# IO_Buffer.net
KiCad netlist of a schematic drawn in EAGLE
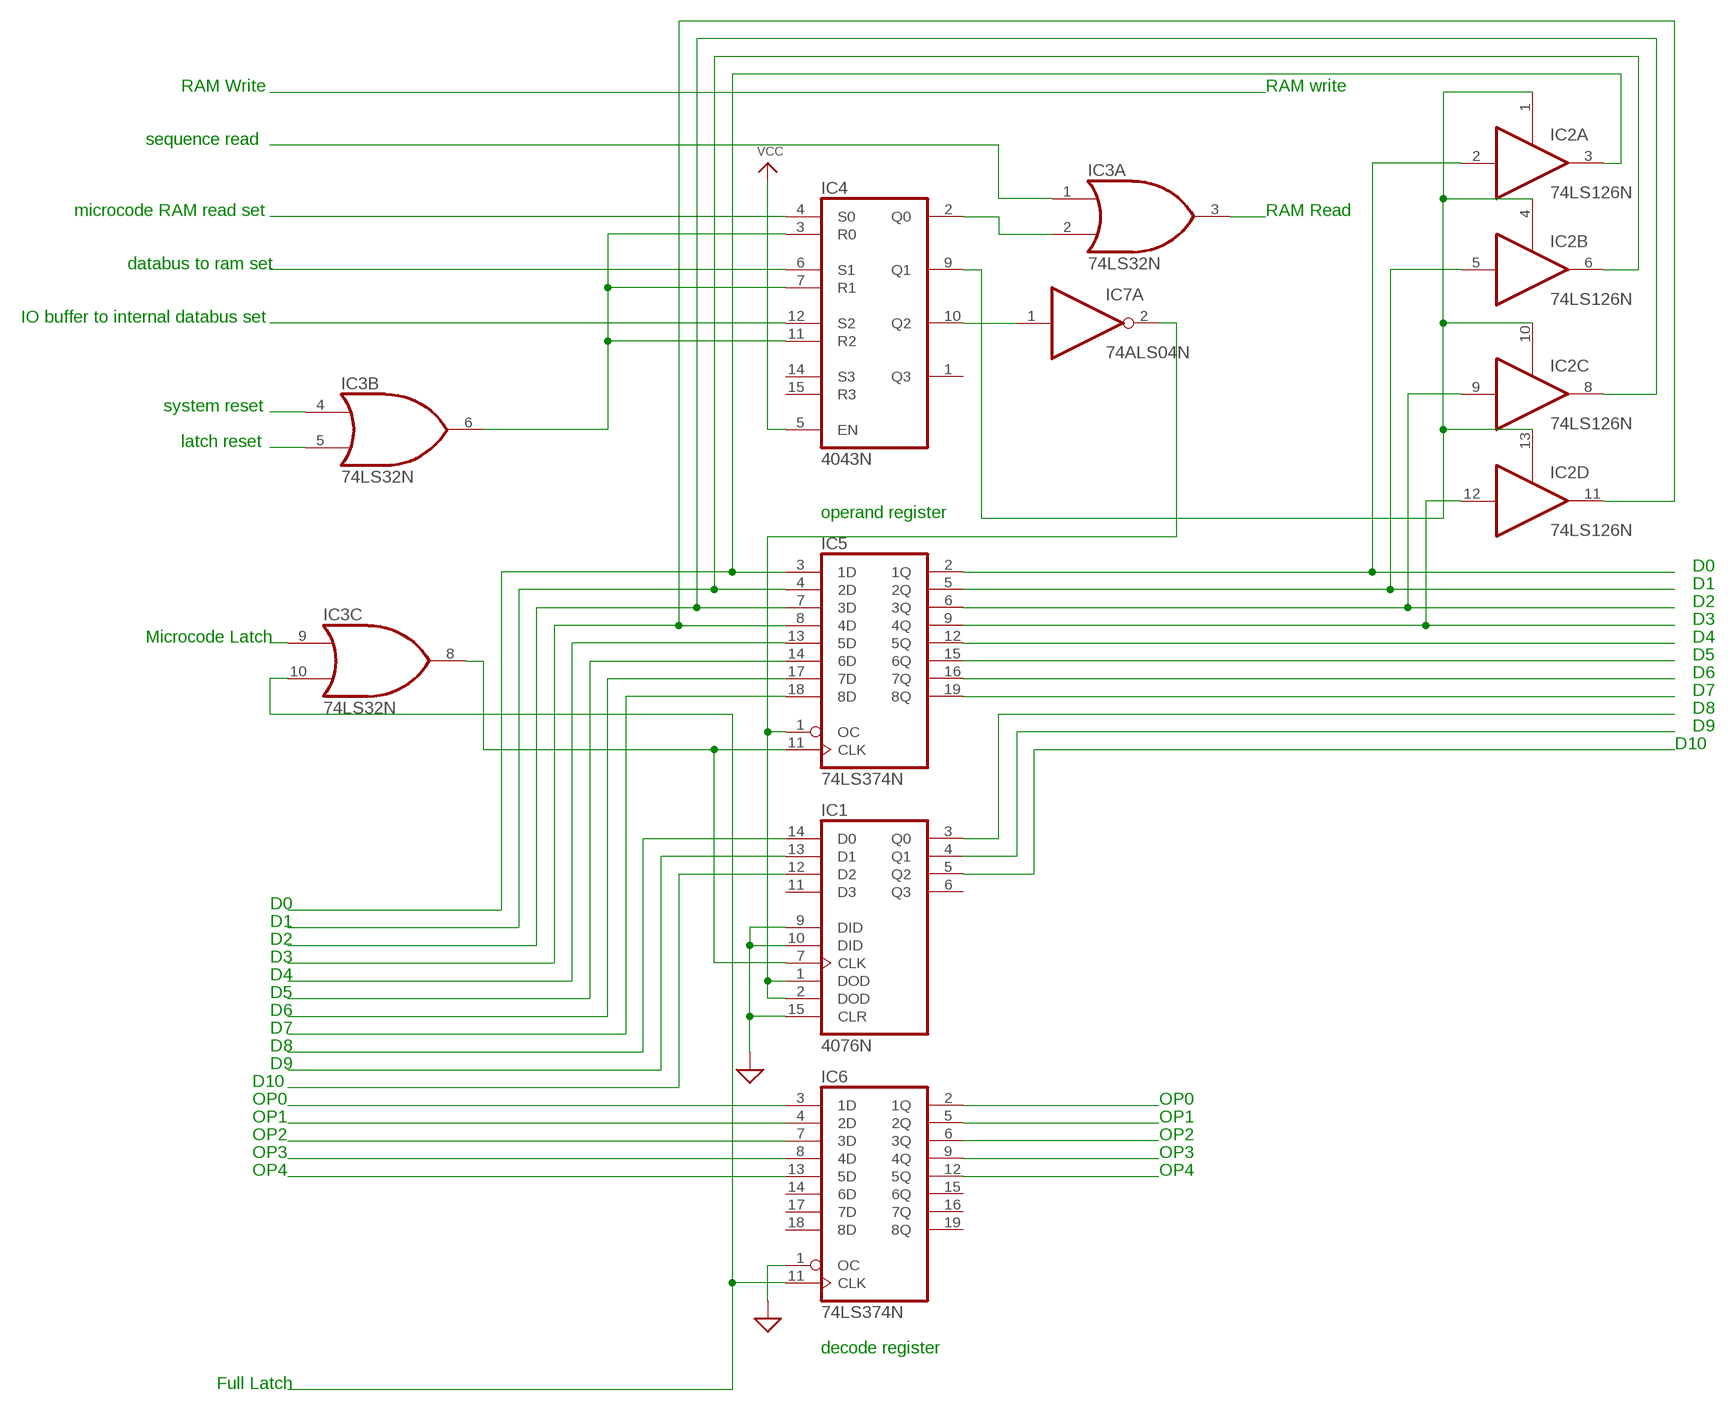
[diagram p0: schematic, sheet 1]

(export (version "E")
  (design (tool "Eeschema 10.0.6"))
  (components
    (comp (ref "IC1")
      (value "4076N")
      (footprint "eagle-import:DIL16")
      (libsource (lib "eagle-import") (part "4076N"))
    )
    (comp (ref "IC2")
      (value "74LS126N")
      (footprint "eagle-import:DIL14")
      (libsource (lib "eagle-import") (part "74126NLS"))
    )
    (comp (ref "IC3")
      (value "74LS32N")
      (footprint "eagle-import:DIL14")
      (libsource (lib "eagle-import") (part "7432NLS"))
    )
    (comp (ref "IC4")
      (value "4043N")
      (footprint "eagle-import:DIL16")
      (libsource (lib "eagle-import") (part "4043N"))
    )
    (comp (ref "IC5")
      (value "74LS374N")
      (footprint "eagle-import:DIL20")
      (libsource (lib "eagle-import") (part "74374NLS"))
    )
    (comp (ref "IC6")
      (value "74LS374N")
      (footprint "eagle-import:DIL20")
      (libsource (lib "eagle-import") (part "74374NLS"))
    )
    (comp (ref "IC7")
      (value "74ALS04N")
      (footprint "eagle-import:DIL14")
      (libsource (lib "eagle-import") (part "7404NALS"))
    )
  )
  (nets
    (net (code "1") (name "Net-(IC1A-CLK)") (class "Default")
      (node (ref "IC1") (pin "7") (pinfunction "CLK_7") (pintype "input"))
      (node (ref "IC3") (pin "8") (pinfunction "O_8") (pintype "output"))
      (node (ref "IC5") (pin "11") (pinfunction "CLK_11") (pintype "input"))
    )
    (net (code "2") (name "Net-(IC2A-I)") (class "Default")
      (node (ref "IC2") (pin "2") (pinfunction "I_2") (pintype "input"))
      (node (ref "IC5") (pin "2") (pinfunction "1Q_2") (pintype "tri_state"))
    )
    (net (code "3") (name "Net-(IC2A-O)") (class "Default")
      (node (ref "IC2") (pin "3") (pinfunction "O_3") (pintype "output"))
      (node (ref "IC5") (pin "3") (pinfunction "1D_3") (pintype "input"))
    )
    (net (code "4") (name "Net-(IC2A-OE)") (class "Default")
      (node (ref "IC2") (pin "1") (pinfunction "OE_1") (pintype "input"))
      (node (ref "IC2") (pin "10") (pinfunction "OE_10") (pintype "input"))
      (node (ref "IC2") (pin "13") (pinfunction "OE_13") (pintype "input"))
      (node (ref "IC2") (pin "4") (pinfunction "OE_4") (pintype "input"))
      (node (ref "IC4") (pin "9") (pinfunction "Q1_9") (pintype "output"))
    )
    (net (code "5") (name "Net-(IC2B-I)") (class "Default")
      (node (ref "IC2") (pin "5") (pinfunction "I_5") (pintype "input"))
      (node (ref "IC5") (pin "5") (pinfunction "2Q_5") (pintype "tri_state"))
    )
    (net (code "6") (name "Net-(IC2B-O)") (class "Default")
      (node (ref "IC2") (pin "6") (pinfunction "O_6") (pintype "output"))
      (node (ref "IC5") (pin "4") (pinfunction "2D_4") (pintype "input"))
    )
    (net (code "7") (name "Net-(IC2C-I)") (class "Default")
      (node (ref "IC2") (pin "9") (pinfunction "I_9") (pintype "input"))
      (node (ref "IC5") (pin "6") (pinfunction "3Q_6") (pintype "tri_state"))
    )
    (net (code "8") (name "Net-(IC2C-O)") (class "Default")
      (node (ref "IC2") (pin "8") (pinfunction "O_8") (pintype "output"))
      (node (ref "IC5") (pin "7") (pinfunction "3D_7") (pintype "input"))
    )
    (net (code "9") (name "Net-(IC2D-I)") (class "Default")
      (node (ref "IC2") (pin "12") (pinfunction "I_12") (pintype "input"))
      (node (ref "IC5") (pin "9") (pinfunction "4Q_9") (pintype "tri_state"))
    )
    (net (code "10") (name "Net-(IC2D-O)") (class "Default")
      (node (ref "IC2") (pin "11") (pinfunction "O_11") (pintype "output"))
      (node (ref "IC5") (pin "8") (pinfunction "4D_8") (pintype "input"))
    )
    (net (code "11") (name "Net-(IC3A-I1)") (class "Default")
      (node (ref "IC3") (pin "2") (pinfunction "I1_2") (pintype "input"))
      (node (ref "IC4") (pin "2") (pinfunction "Q0_2") (pintype "output"))
    )
    (net (code "12") (name "Net-(IC3B-O)") (class "Default")
      (node (ref "IC3") (pin "6") (pinfunction "O_6") (pintype "output"))
      (node (ref "IC4") (pin "11") (pinfunction "R2_11") (pintype "input"))
      (node (ref "IC4") (pin "3") (pinfunction "R0_3") (pintype "input"))
      (node (ref "IC4") (pin "7") (pinfunction "R1_7") (pintype "input"))
    )
    (net (code "13") (name "Net-(IC3C-I1)") (class "Default")
      (node (ref "IC3") (pin "10") (pinfunction "I1_10") (pintype "input"))
      (node (ref "IC6") (pin "11") (pinfunction "CLK_11") (pintype "input"))
    )
    (net (code "14") (name "Net-(IC4A-Q2)") (class "Default")
      (node (ref "IC4") (pin "10") (pinfunction "Q2_10") (pintype "output"))
      (node (ref "IC7") (pin "1") (pinfunction "I_1") (pintype "input"))
    )
    (net (code "15") (name "Net-(IC5A-OC)") (class "Default")
      (node (ref "IC1") (pin "1") (pinfunction "DOD_1") (pintype "input"))
      (node (ref "IC1") (pin "2") (pinfunction "DOD_2") (pintype "input"))
      (node (ref "IC5") (pin "1") (pinfunction "OC_1") (pintype "input"))
      (node (ref "IC7") (pin "2") (pinfunction "O_2") (pintype "output"))
    )
    (net (code "16") (name "SUP") (class "Default")
      (node (ref "IC1") (pin "10") (pinfunction "DID_10") (pintype "input"))
      (node (ref "IC1") (pin "15") (pinfunction "CLR_15") (pintype "input"))
      (node (ref "IC1") (pin "9") (pinfunction "DID_9") (pintype "input"))
      (node (ref "IC6") (pin "1") (pinfunction "OC_1") (pintype "input"))
    )
    (net (code "17") (name "VCC") (class "Default")
      (node (ref "IC4") (pin "5") (pinfunction "EN_5") (pintype "input"))
    )
    (net (code "18") (name "unconnected-(IC1A-D0-Pad14)") (class "Default")
      (node (ref "IC1") (pin "14") (pinfunction "D0_14") (pintype "input"))
    )
    (net (code "19") (name "unconnected-(IC1A-D1-Pad13)") (class "Default")
      (node (ref "IC1") (pin "13") (pinfunction "D1_13") (pintype "input"))
    )
    (net (code "20") (name "unconnected-(IC1A-D2-Pad12)") (class "Default")
      (node (ref "IC1") (pin "12") (pinfunction "D2_12") (pintype "input"))
    )
    (net (code "21") (name "unconnected-(IC1A-D3-Pad11)") (class "Default")
      (node (ref "IC1") (pin "11") (pinfunction "D3_11") (pintype "input"))
    )
    (net (code "22") (name "unconnected-(IC1A-Q0-Pad3)") (class "Default")
      (node (ref "IC1") (pin "3") (pinfunction "Q0_3") (pintype "output"))
    )
    (net (code "23") (name "unconnected-(IC1A-Q1-Pad4)") (class "Default")
      (node (ref "IC1") (pin "4") (pinfunction "Q1_4") (pintype "output"))
    )
    (net (code "24") (name "unconnected-(IC1A-Q2-Pad5)") (class "Default")
      (node (ref "IC1") (pin "5") (pinfunction "Q2_5") (pintype "output"))
    )
    (net (code "25") (name "unconnected-(IC1A-Q3-Pad6)") (class "Default")
      (node (ref "IC1") (pin "6") (pinfunction "Q3_6") (pintype "output"))
    )
    (net (code "26") (name "unconnected-(IC3A-I0-Pad1)") (class "Default")
      (node (ref "IC3") (pin "1") (pinfunction "I0_1") (pintype "input"))
    )
    (net (code "27") (name "unconnected-(IC3A-O-Pad3)") (class "Default")
      (node (ref "IC3") (pin "3") (pinfunction "O_3") (pintype "output"))
    )
    (net (code "28") (name "unconnected-(IC3B-I0-Pad4)") (class "Default")
      (node (ref "IC3") (pin "4") (pinfunction "I0_4") (pintype "input"))
    )
    (net (code "29") (name "unconnected-(IC3B-I1-Pad5)") (class "Default")
      (node (ref "IC3") (pin "5") (pinfunction "I1_5") (pintype "input"))
    )
    (net (code "30") (name "unconnected-(IC3C-I0-Pad9)") (class "Default")
      (node (ref "IC3") (pin "9") (pinfunction "I0_9") (pintype "input"))
    )
    (net (code "31") (name "unconnected-(IC4A-Q3-Pad1)") (class "Default")
      (node (ref "IC4") (pin "1") (pinfunction "Q3_1") (pintype "output"))
    )
    (net (code "32") (name "unconnected-(IC4A-R3-Pad15)") (class "Default")
      (node (ref "IC4") (pin "15") (pinfunction "R3_15") (pintype "input"))
    )
    (net (code "33") (name "unconnected-(IC4A-S0-Pad4)") (class "Default")
      (node (ref "IC4") (pin "4") (pinfunction "S0_4") (pintype "input"))
    )
    (net (code "34") (name "unconnected-(IC4A-S1-Pad6)") (class "Default")
      (node (ref "IC4") (pin "6") (pinfunction "S1_6") (pintype "input"))
    )
    (net (code "35") (name "unconnected-(IC4A-S2-Pad12)") (class "Default")
      (node (ref "IC4") (pin "12") (pinfunction "S2_12") (pintype "input"))
    )
    (net (code "36") (name "unconnected-(IC4A-S3-Pad14)") (class "Default")
      (node (ref "IC4") (pin "14") (pinfunction "S3_14") (pintype "input"))
    )
    (net (code "37") (name "unconnected-(IC5A-5D-Pad13)") (class "Default")
      (node (ref "IC5") (pin "13") (pinfunction "5D_13") (pintype "input"))
    )
    (net (code "38") (name "unconnected-(IC5A-5Q-Pad12)") (class "Default")
      (node (ref "IC5") (pin "12") (pinfunction "5Q_12") (pintype "tri_state"))
    )
    (net (code "39") (name "unconnected-(IC5A-6D-Pad14)") (class "Default")
      (node (ref "IC5") (pin "14") (pinfunction "6D_14") (pintype "input"))
    )
    (net (code "40") (name "unconnected-(IC5A-6Q-Pad15)") (class "Default")
      (node (ref "IC5") (pin "15") (pinfunction "6Q_15") (pintype "tri_state"))
    )
    (net (code "41") (name "unconnected-(IC5A-7D-Pad17)") (class "Default")
      (node (ref "IC5") (pin "17") (pinfunction "7D_17") (pintype "input"))
    )
    (net (code "42") (name "unconnected-(IC5A-7Q-Pad16)") (class "Default")
      (node (ref "IC5") (pin "16") (pinfunction "7Q_16") (pintype "tri_state"))
    )
    (net (code "43") (name "unconnected-(IC5A-8D-Pad18)") (class "Default")
      (node (ref "IC5") (pin "18") (pinfunction "8D_18") (pintype "input"))
    )
    (net (code "44") (name "unconnected-(IC5A-8Q-Pad19)") (class "Default")
      (node (ref "IC5") (pin "19") (pinfunction "8Q_19") (pintype "tri_state"))
    )
    (net (code "45") (name "unconnected-(IC6A-1D-Pad3)") (class "Default")
      (node (ref "IC6") (pin "3") (pinfunction "1D_3") (pintype "input"))
    )
    (net (code "46") (name "unconnected-(IC6A-1Q-Pad2)") (class "Default")
      (node (ref "IC6") (pin "2") (pinfunction "1Q_2") (pintype "tri_state"))
    )
    (net (code "47") (name "unconnected-(IC6A-2D-Pad4)") (class "Default")
      (node (ref "IC6") (pin "4") (pinfunction "2D_4") (pintype "input"))
    )
    (net (code "48") (name "unconnected-(IC6A-2Q-Pad5)") (class "Default")
      (node (ref "IC6") (pin "5") (pinfunction "2Q_5") (pintype "tri_state"))
    )
    (net (code "49") (name "unconnected-(IC6A-3D-Pad7)") (class "Default")
      (node (ref "IC6") (pin "7") (pinfunction "3D_7") (pintype "input"))
    )
    (net (code "50") (name "unconnected-(IC6A-3Q-Pad6)") (class "Default")
      (node (ref "IC6") (pin "6") (pinfunction "3Q_6") (pintype "tri_state"))
    )
    (net (code "51") (name "unconnected-(IC6A-4D-Pad8)") (class "Default")
      (node (ref "IC6") (pin "8") (pinfunction "4D_8") (pintype "input"))
    )
    (net (code "52") (name "unconnected-(IC6A-4Q-Pad9)") (class "Default")
      (node (ref "IC6") (pin "9") (pinfunction "4Q_9") (pintype "tri_state"))
    )
    (net (code "53") (name "unconnected-(IC6A-5D-Pad13)") (class "Default")
      (node (ref "IC6") (pin "13") (pinfunction "5D_13") (pintype "input"))
    )
    (net (code "54") (name "unconnected-(IC6A-5Q-Pad12)") (class "Default")
      (node (ref "IC6") (pin "12") (pinfunction "5Q_12") (pintype "tri_state"))
    )
    (net (code "55") (name "unconnected-(IC6A-6D-Pad14)") (class "Default")
      (node (ref "IC6") (pin "14") (pinfunction "6D_14") (pintype "input"))
    )
    (net (code "56") (name "unconnected-(IC6A-6Q-Pad15)") (class "Default")
      (node (ref "IC6") (pin "15") (pinfunction "6Q_15") (pintype "tri_state"))
    )
    (net (code "57") (name "unconnected-(IC6A-7D-Pad17)") (class "Default")
      (node (ref "IC6") (pin "17") (pinfunction "7D_17") (pintype "input"))
    )
    (net (code "58") (name "unconnected-(IC6A-7Q-Pad16)") (class "Default")
      (node (ref "IC6") (pin "16") (pinfunction "7Q_16") (pintype "tri_state"))
    )
    (net (code "59") (name "unconnected-(IC6A-8D-Pad18)") (class "Default")
      (node (ref "IC6") (pin "18") (pinfunction "8D_18") (pintype "input"))
    )
    (net (code "60") (name "unconnected-(IC6A-8Q-Pad19)") (class "Default")
      (node (ref "IC6") (pin "19") (pinfunction "8Q_19") (pintype "tri_state"))
    )
  )
)
